# Adafruit_TSMP96000_Code_Learning_IR_Brea.net
KiCad netlist of a schematic drawn in EAGLE
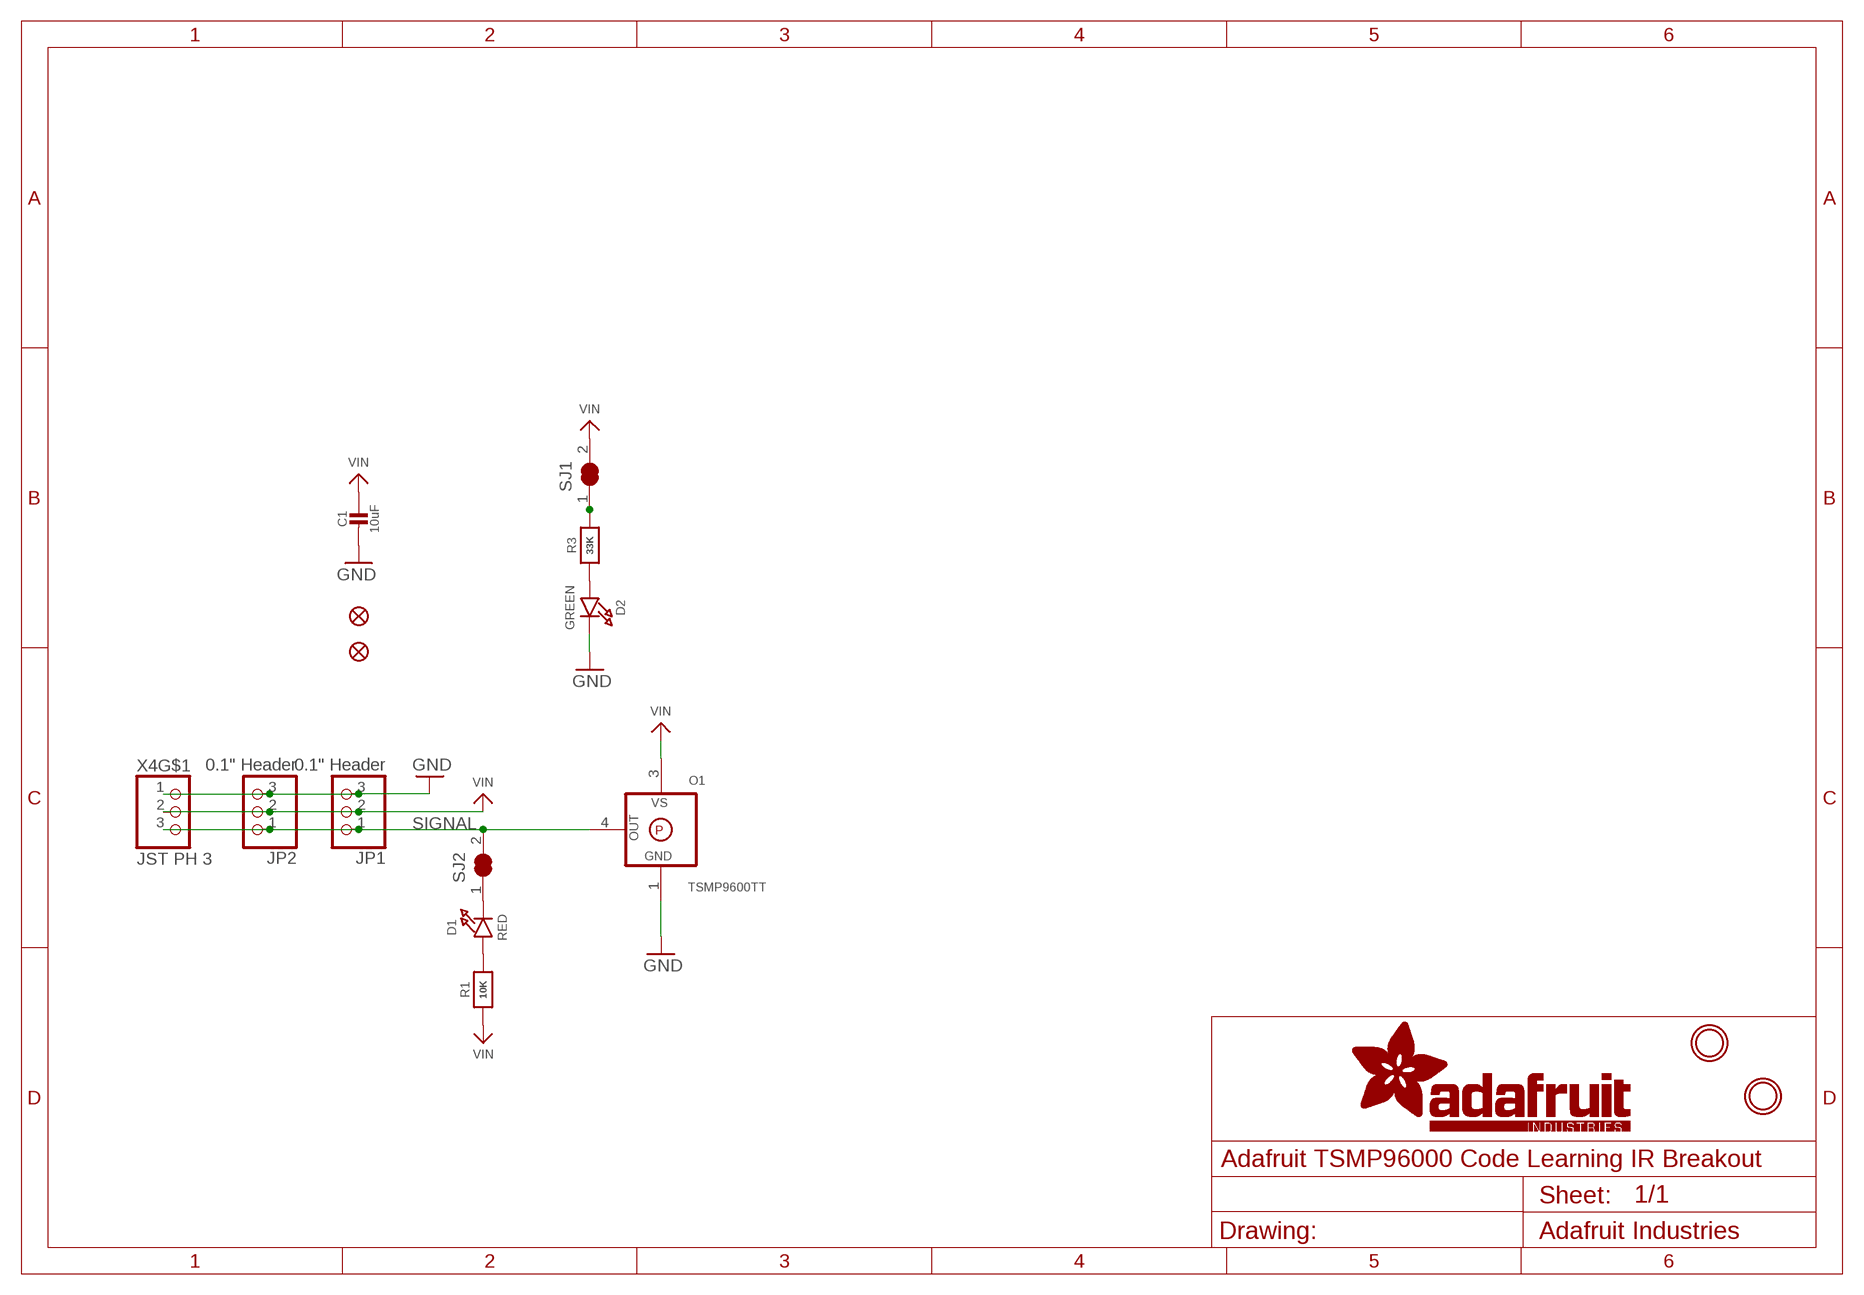
[diagram p0: schematic, sheet 1]

(export (version "E")
  (design (tool "Eeschema 10.0.6"))
  (components
    (comp (ref "C1")
      (value "10uF")
      (footprint "eagle-import:0805-NO")
      (libsource (lib "eagle-import") (part "CAP_CERAMIC0805-NOOUTLINE"))
    )
    (comp (ref "D1")
      (value "RED")
      (footprint "eagle-import:CHIPLED_0603_NOOUTLINE")
      (libsource (lib "eagle-import") (part "LED0603_NOOUTLINE"))
    )
    (comp (ref "D2")
      (value "GREEN")
      (footprint "eagle-import:CHIPLED_0603_NOOUTLINE")
      (libsource (lib "eagle-import") (part "LED0603_NOOUTLINE"))
    )
    (comp (ref "FID2")
      (value "FIDUCIAL_1MM")
      (footprint "eagle-import:FIDUCIAL_1MM")
      (libsource (lib "eagle-import") (part "FIDUCIAL_1MM"))
    )
    (comp (ref "FID3")
      (value "FIDUCIAL_1MM")
      (footprint "eagle-import:FIDUCIAL_1MM")
      (libsource (lib "eagle-import") (part "FIDUCIAL_1MM"))
    )
    (comp (ref "JP1")
      (value "0.1\" Header")
      (footprint "eagle-import:1X03_OVAL")
      (libsource (lib "eagle-import") (part "HEADER-1X3"))
    )
    (comp (ref "JP2")
      (value "0.1\" Header")
      (footprint "eagle-import:1X03_ROUND_76")
      (libsource (lib "eagle-import") (part "HEADER-1X376MIL"))
    )
    (comp (ref "O1")
      (value "TSMP9600TT")
      (footprint "eagle-import:VISHAY_PANHEAD_TT")
      (libsource (lib "eagle-import") (part "GENERIC_IR_RECV_PANHEAD_TT"))
    )
    (comp (ref "R1")
      (value "10K")
      (footprint "eagle-import:0603-NO")
      (libsource (lib "eagle-import") (part "RESISTOR_0603_NOOUT"))
    )
    (comp (ref "R3")
      (value "33K")
      (footprint "eagle-import:0603-NO")
      (libsource (lib "eagle-import") (part "RESISTOR_0603_NOOUT"))
    )
    (comp (ref "SJ1")
      (value "SOLDERJUMPER_CLOSED")
      (footprint "eagle-import:SOLDERJUMPER_CLOSEDWIRE")
      (libsource (lib "eagle-import") (part "SOLDERJUMPER_CLOSED"))
    )
    (comp (ref "SJ2")
      (value "SOLDERJUMPER_CLOSED")
      (footprint "eagle-import:SOLDERJUMPER_CLOSEDWIRE")
      (libsource (lib "eagle-import") (part "SOLDERJUMPER_CLOSED"))
    )
    (comp (ref "U$1")
      (value "MOUNTINGHOLE2.5")
      (footprint "eagle-import:MOUNTINGHOLE_2.5_PLATED")
      (libsource (lib "eagle-import") (part "MOUNTINGHOLE2.5"))
    )
    (comp (ref "U$8")
      (value "MOUNTINGHOLE2.5")
      (footprint "eagle-import:MOUNTINGHOLE_2.5_PLATED")
      (libsource (lib "eagle-import") (part "MOUNTINGHOLE2.5"))
    )
    (comp (ref "X4")
      (value "JST PH 3")
      (footprint "eagle-import:JSTPH3")
      (libsource (lib "eagle-import") (part "CON_JST_PH_3PIN"))
    )
  )
  (nets
    (net (code "1") (name "/SIGNAL") (class "Default")
      (node (ref "JP1") (pin "1") (pinfunction "1_1") (pintype "passive"))
      (node (ref "JP2") (pin "1") (pinfunction "1_1") (pintype "passive"))
      (node (ref "O1") (pin "4") (pinfunction "OUT_4") (pintype "output"))
      (node (ref "SJ2") (pin "2") (pinfunction "2_2") (pintype "passive"))
      (node (ref "X4") (pin "3") (pinfunction "3_3") (pintype "passive"))
    )
    (net (code "2") (name "GND") (class "Default")
      (node (ref "C1") (pin "2") (pinfunction "2_2") (pintype "passive"))
      (node (ref "D2") (pin "C") (pinfunction "C_C") (pintype "passive"))
      (node (ref "JP1") (pin "3") (pinfunction "3_3") (pintype "passive"))
      (node (ref "JP2") (pin "3") (pinfunction "3_3") (pintype "passive"))
      (node (ref "O1") (pin "1") (pinfunction "GND_1") (pintype "power_in"))
      (node (ref "X4") (pin "1") (pinfunction "1_1") (pintype "passive"))
    )
    (net (code "3") (name "Net-(D1-PadA)") (class "Default")
      (node (ref "D1") (pin "A") (pinfunction "A_A") (pintype "passive"))
      (node (ref "R1") (pin "2") (pinfunction "2_2") (pintype "passive"))
    )
    (net (code "4") (name "Net-(D1-PadC)") (class "Default")
      (node (ref "D1") (pin "C") (pinfunction "C_C") (pintype "passive"))
      (node (ref "SJ2") (pin "1") (pinfunction "1_1") (pintype "passive"))
    )
    (net (code "5") (name "Net-(D2-PadA)") (class "Default")
      (node (ref "D2") (pin "A") (pinfunction "A_A") (pintype "passive"))
      (node (ref "R3") (pin "1") (pinfunction "1_1") (pintype "passive"))
    )
    (net (code "6") (name "Net-(R3-Pad2)") (class "Default")
      (node (ref "R3") (pin "2") (pinfunction "2_2") (pintype "passive"))
      (node (ref "SJ1") (pin "1") (pinfunction "1_1") (pintype "passive"))
    )
    (net (code "7") (name "VIN") (class "Default")
      (node (ref "C1") (pin "1") (pinfunction "1_1") (pintype "passive"))
      (node (ref "JP1") (pin "2") (pinfunction "2_2") (pintype "passive"))
      (node (ref "JP2") (pin "2") (pinfunction "2_2") (pintype "passive"))
      (node (ref "O1") (pin "3") (pinfunction "VS_3") (pintype "power_in"))
      (node (ref "R1") (pin "1") (pinfunction "1_1") (pintype "passive"))
      (node (ref "SJ1") (pin "2") (pinfunction "2_2") (pintype "passive"))
      (node (ref "X4") (pin "2") (pinfunction "2_2") (pintype "passive"))
    )
  )
)
